# JTAG_Reset_Connection.net
KiCad netlist of a schematic drawn in Altium Designer
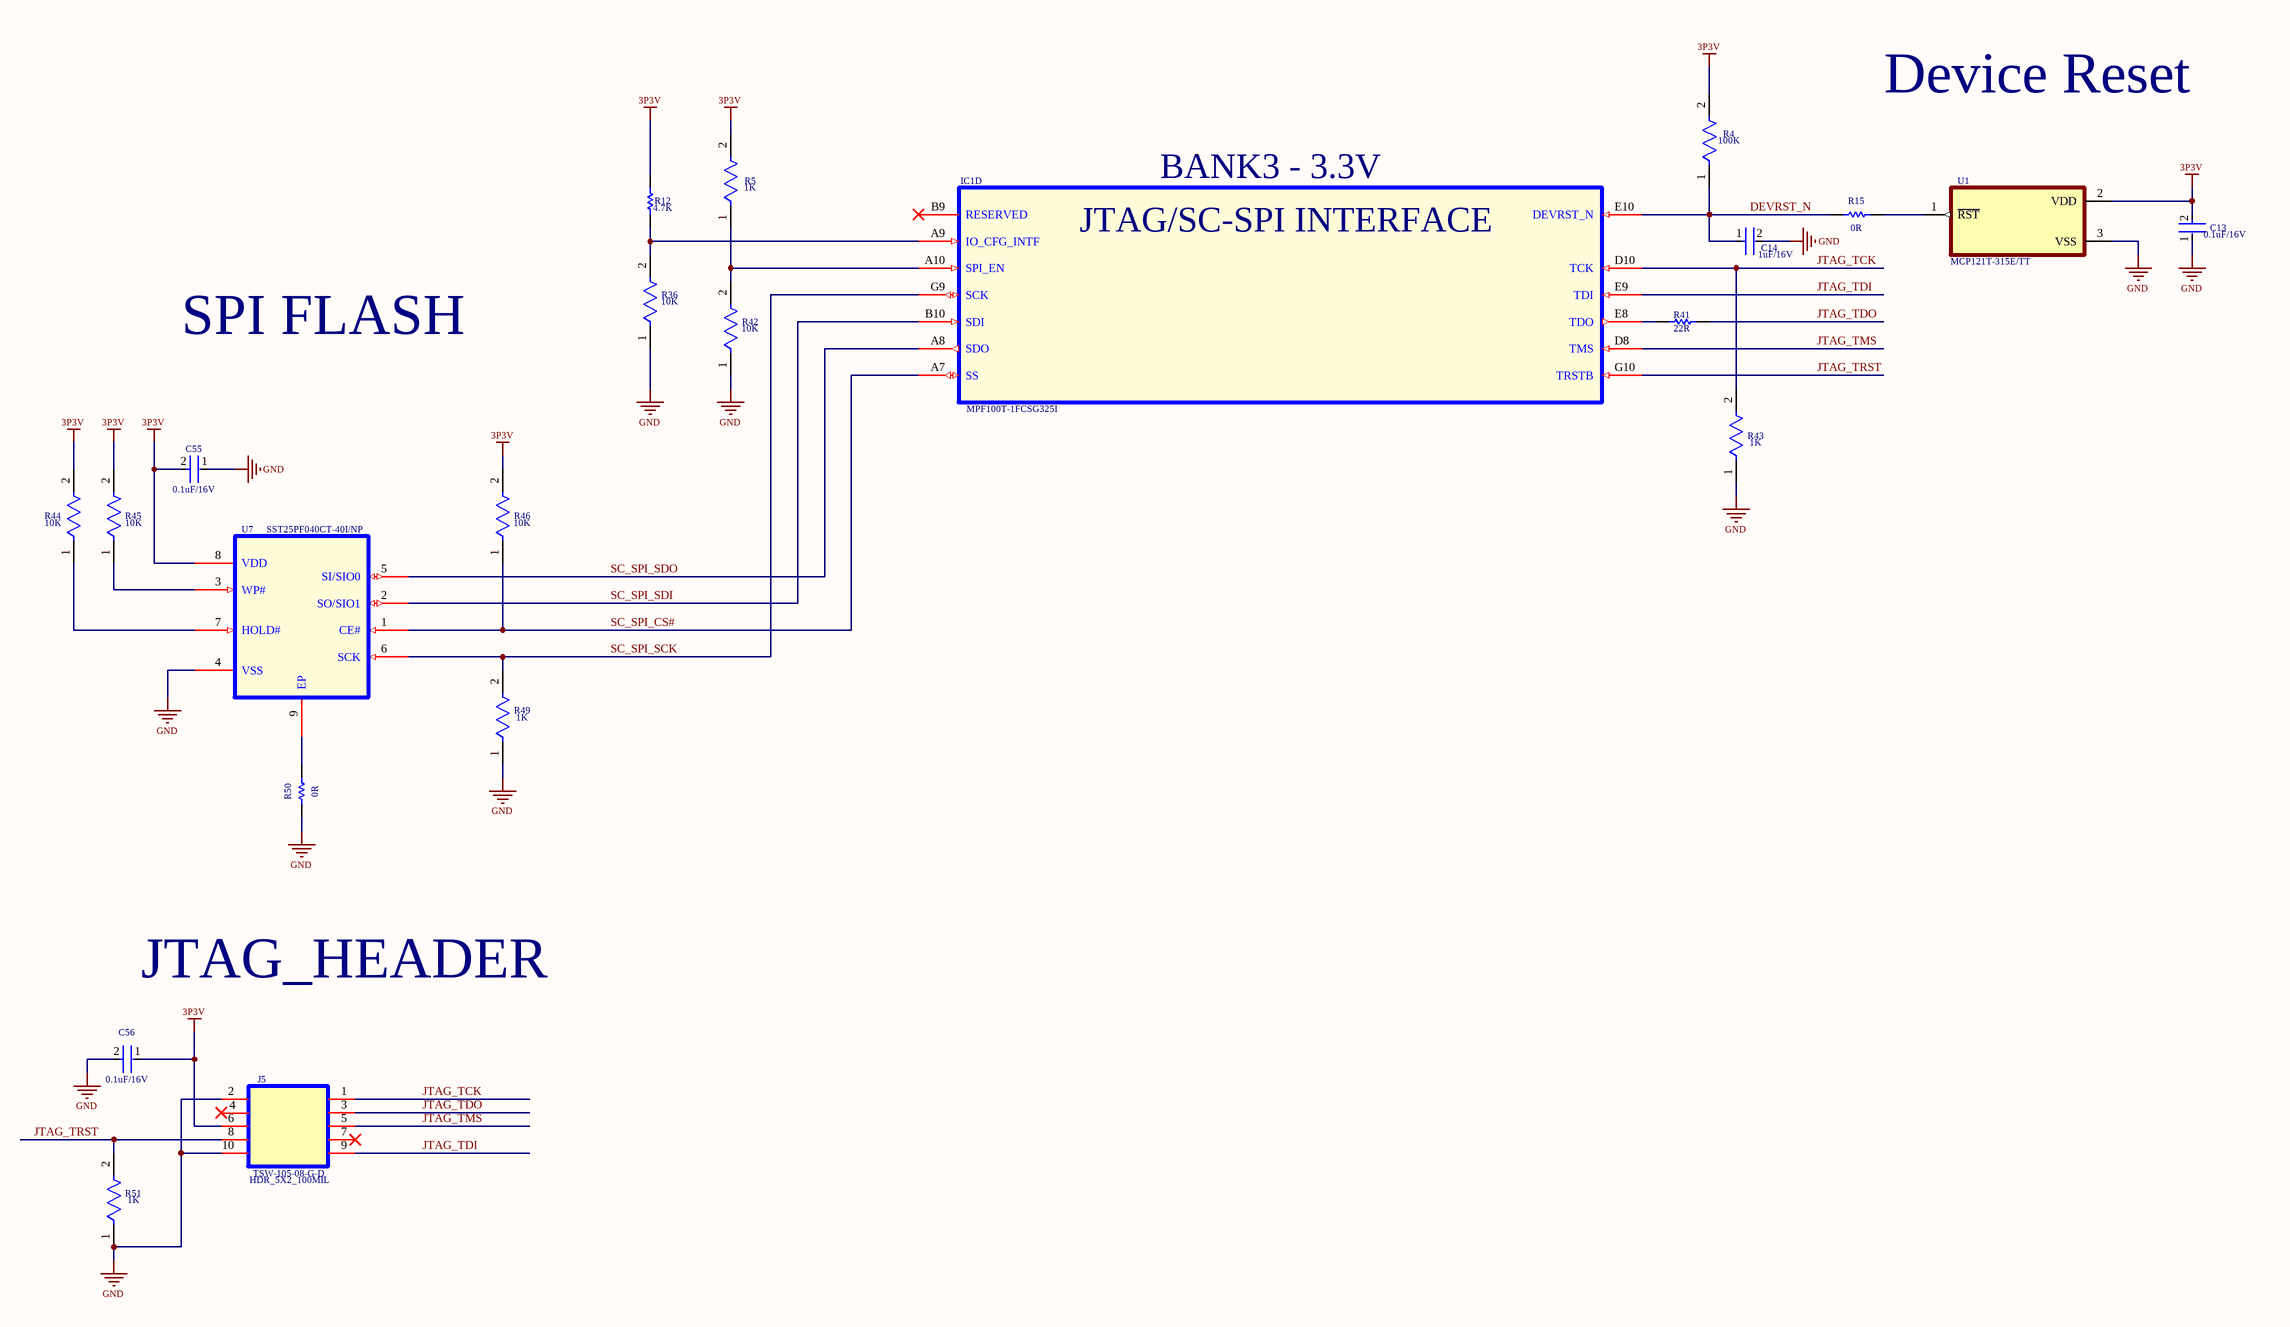
[diagram p0: JTAG & Reset Connection.SchDoc]

(export (version "E")
  (design (tool "Eeschema 10.0.6"))
  (components
    (comp (ref "C13")
      (value "0.1uF/16V")
      (footprint "FP-GRM15-MFG")
      (description "CAP CER 0.1UF 16V X7R 0402")
      (fields (field (name "MANUFACTURER PART NUMBER") "GRM155R71C104KA88D") (field (name "TOLERANCE") "10%"))
      (libsource (lib "Altium Content Vault") (part "236180d848d6139a670b325ea6854c9"))
    )
    (comp (ref "C14")
      (value "1uF/16V")
      (footprint "FP-0402-L_1_0_0_05-W_0_5-IPC_A")
      (description "None")
      (fields (field (name "TOLERANCE") "10%"))
      (libsource (lib "Altium Content Vault") (part "b4654b650e69147ec39a6b967a45e02"))
    )
    (comp (ref "C55")
      (value "0.1uF/16V")
      (footprint "FP-GRM15-MFG")
      (description "CAP CER 0.1UF 16V X7R 0402")
      (fields (field (name "MANUFACTURER PART NUMBER") "GRM155R71C104KA88D") (field (name "TOLERANCE") "10%"))
      (libsource (lib "Altium Content Vault") (part "236180d848d6139a670b325ea6854c9"))
    )
    (comp (ref "C56")
      (value "0.1uF/16V")
      (footprint "FP-GRM15-MFG")
      (description "CAP CER 0.1UF 16V X7R 0402")
      (fields (field (name "MANUFACTURER PART NUMBER") "GRM155R71C104KA88D") (field (name "TOLERANCE") "10%"))
      (libsource (lib "Altium Content Vault") (part "236180d848d6139a670b325ea6854c9"))
    )
    (comp (ref "IC1")
      (value "MPF100T-1FCSG325I")
      (footprint "PCB_Display_Doru:MPF100T-1FCSG325I")
      (fields (field (name "PART_NUMBER") "J00001"))
      (libsource (lib "PCB_Display_Doru") (part "MPF100T-1FCSG325I"))
    )
    (comp (ref "J5")
      (value "TSW-105-08-G-D")
      (footprint "PCB_Display_Doru:TSW-105-08-G-D")
      (description "Jumper")
      (fields (field (name "PART_NUMBER") "J00001") (field (name "PARAMETER 1") "HDR_5X2_100MIL"))
      (libsource (lib "PCB_Display_Doru") (part "TSW-105-08-G-D"))
    )
    (comp (ref "R4")
      (value "100K")
      (footprint "FP-RC0603-0_55-MFG")
      (description "RES SMD 100K OHM 1% 1/10W 0603")
      (fields (field (name "TOLERANCE") "1%"))
      (libsource (lib "Altium Content Vault") (part "1029c3af85768c4190bb7ad29bc67b5"))
    )
    (comp (ref "R5")
      (value "1K")
      (footprint "FP-RC0603-0_55-IPC_C")
      (description "RES 1K OHM 1% 1/10W 0603")
      (fields (field (name "TOLERANCE") "1%"))
      (libsource (lib "Altium Content Vault") (part "1029c3af85768c4190bb7ad29bc67b5"))
    )
    (comp (ref "R12")
      (value "4.7K")
      (footprint "RESC1608X55X25LL10T15")
      (description "Chip Resistor, 4.7 KOhm, +/- 1%, 0.1 W, -55 to 155 degC, 0603 (1608 Metric), RoHS, Tape and Reel")
      (fields (field (name "MANUFACTURER") "Yageo") (field (name "TOLERANCE") "1%"))
      (libsource (lib "Altium Content Vault") (part "RES-2"))
    )
    (comp (ref "R15")
      (value "0R")
      (footprint "RESC1005X40X25NL05T10")
      (fields (field (name "MANUFACTURER") "Yageo / Phycomp") (field (name "PART NUMBER") "RC0402JR-070RL"))
      (libsource (lib "Altium Content Vault") (part "RES"))
    )
    (comp (ref "R36")
      (value "10K")
      (footprint "FP-RC0603-0_55-IPC_C")
      (description "RES 10K OHM 1% 1/10W 0603")
      (fields (field (name "TOLERANCE") "1%"))
      (libsource (lib "Altium Content Vault") (part "1029c3af85768c4190bb7ad29bc67b5"))
    )
    (comp (ref "R41")
      (value "22R")
      (footprint "RESC1005X40X25LL05T10")
      (fields (field (name "MANUFACTURER") "Yageo / Phycomp") (field (name "PART NUMBER") "RC0402FR-0722RL"))
      (libsource (lib "Altium Content Vault") (part "RES"))
    )
    (comp (ref "R42")
      (value "10K")
      (footprint "FP-RC0603-0_55-IPC_C")
      (description "RES 10K OHM 1% 1/10W 0603")
      (fields (field (name "TOLERANCE") "1%"))
      (libsource (lib "Altium Content Vault") (part "1029c3af85768c4190bb7ad29bc67b5"))
    )
    (comp (ref "R43")
      (value "1K")
      (footprint "FP-RC0603-0_55-IPC_C")
      (description "RES 1K OHM 1% 1/10W 0603")
      (fields (field (name "TOLERANCE") "1%"))
      (libsource (lib "Altium Content Vault") (part "1029c3af85768c4190bb7ad29bc67b5"))
    )
    (comp (ref "R44")
      (value "10K")
      (footprint "FP-RC0603-0_55-IPC_C")
      (description "RES 10K OHM 1% 1/10W 0603")
      (fields (field (name "TOLERANCE") "1%"))
      (libsource (lib "Altium Content Vault") (part "1029c3af85768c4190bb7ad29bc67b5"))
    )
    (comp (ref "R45")
      (value "10K")
      (footprint "FP-RC0603-0_55-IPC_C")
      (description "RES 10K OHM 1% 1/10W 0603")
      (fields (field (name "TOLERANCE") "1%"))
      (libsource (lib "Altium Content Vault") (part "1029c3af85768c4190bb7ad29bc67b5"))
    )
    (comp (ref "R46")
      (value "10K")
      (footprint "FP-RC0603-0_55-IPC_C")
      (description "RES 10K OHM 1% 1/10W 0603")
      (fields (field (name "TOLERANCE") "1%"))
      (libsource (lib "Altium Content Vault") (part "1029c3af85768c4190bb7ad29bc67b5"))
    )
    (comp (ref "R49")
      (value "1K")
      (footprint "FP-RC0603-0_55-IPC_C")
      (description "RES 1K OHM 1% 1/10W 0603")
      (fields (field (name "TOLERANCE") "1%"))
      (libsource (lib "Altium Content Vault") (part "1029c3af85768c4190bb7ad29bc67b5"))
    )
    (comp (ref "R50")
      (value "0R")
      (footprint "RESC1005X40X25NL05T10")
      (fields (field (name "MANUFACTURER") "Yageo / Phycomp") (field (name "PART NUMBER") "RC0402JR-070RL"))
      (libsource (lib "Altium Content Vault") (part "RES"))
    )
    (comp (ref "R51")
      (value "1K")
      (footprint "FP-RC0603-0_55-IPC_C")
      (description "RES 1K OHM 1% 1/10W 0603")
      (fields (field (name "TOLERANCE") "1%"))
      (libsource (lib "Altium Content Vault") (part "1029c3af85768c4190bb7ad29bc67b5"))
    )
    (comp (ref "U1")
      (value "MCP121T-315E/TT")
      (footprint "PCB_Display_Doru:MCP121T-315E/TT")
      (description "Jumper")
      (fields (field (name "PART_NUMBER") "J00001"))
      (libsource (lib "PCB_Display_Doru") (part "MCP121T-315E/TT"))
    )
    (comp (ref "U7")
      (value "SST25PF040CT-40I/NP")
      (footprint "PCB_Display_Doru:SST25PF040CT-40I/NP")
      (description "Jumper")
      (fields (field (name "PART_NUMBER") "J00001"))
      (libsource (lib "PCB_Display_Doru") (part "SST25PF040CT-40I/NP"))
    )
  )
  (nets
    (net (code "1") (name "/DEVRST_N") (class "Default")
      (node (ref "C14") (pin "1") (pinfunction "1_1") (pintype "passive"))
      (node (ref "IC1") (pin "E10") (pinfunction "DEVRST_N_E10") (pintype "input"))
      (node (ref "R15") (pin "1") (pinfunction "1_1") (pintype "passive"))
      (node (ref "R4") (pin "1") (pinfunction "1_1") (pintype "passive"))
    )
    (net (code "2") (name "/JTAG_TCK") (class "Default")
      (node (ref "IC1") (pin "D10") (pinfunction "TCK_D10") (pintype "input"))
      (node (ref "J5") (pin "1") (pinfunction "02_1") (pintype "passive"))
      (node (ref "R43") (pin "2") (pinfunction "2_2") (pintype "passive"))
    )
    (net (code "3") (name "/JTAG_TDI") (class "Default")
      (node (ref "IC1") (pin "E9") (pinfunction "TDI_E9") (pintype "input"))
      (node (ref "J5") (pin "9") (pinfunction "10_9") (pintype "passive"))
    )
    (net (code "4") (name "/JTAG_TDO") (class "Default")
      (node (ref "J5") (pin "3") (pinfunction "04_3") (pintype "passive"))
      (node (ref "R41") (pin "1") (pinfunction "1_1") (pintype "passive"))
    )
    (net (code "5") (name "/JTAG_TMS") (class "Default")
      (node (ref "IC1") (pin "D8") (pinfunction "TMS_D8") (pintype "input"))
      (node (ref "J5") (pin "5") (pinfunction "06_5") (pintype "passive"))
    )
    (net (code "6") (name "/JTAG_TRST") (class "Default")
      (node (ref "IC1") (pin "G10") (pinfunction "TRSTB_G10") (pintype "input"))
      (node (ref "J5") (pin "8") (pinfunction "07_8") (pintype "passive"))
      (node (ref "R51") (pin "2") (pinfunction "2_2") (pintype "passive"))
    )
    (net (code "7") (name "/SC_SPI_CS#") (class "Default")
      (node (ref "IC1") (pin "A7") (pinfunction "SS_A7") (pintype "bidirectional"))
      (node (ref "R46") (pin "1") (pinfunction "1_1") (pintype "passive"))
      (node (ref "U7") (pin "1") (pinfunction "CE#_1") (pintype "input"))
    )
    (net (code "8") (name "/SC_SPI_SCK") (class "Default")
      (node (ref "IC1") (pin "G9") (pinfunction "SCK_G9") (pintype "bidirectional"))
      (node (ref "R49") (pin "2") (pinfunction "2_2") (pintype "passive"))
      (node (ref "U7") (pin "6") (pinfunction "SCK_6") (pintype "input"))
    )
    (net (code "9") (name "/SC_SPI_SDI") (class "Default")
      (node (ref "IC1") (pin "B10") (pinfunction "SDI_B10") (pintype "input"))
      (node (ref "U7") (pin "2") (pinfunction "SO/SIO1_2") (pintype "bidirectional"))
    )
    (net (code "10") (name "/SC_SPI_SDO") (class "Default")
      (node (ref "IC1") (pin "A8") (pinfunction "SDO_A8") (pintype "output"))
      (node (ref "U7") (pin "5") (pinfunction "SI/SIO0_5") (pintype "bidirectional"))
    )
    (net (code "11") (name "3P3V") (class "Default")
      (node (ref "C13") (pin "2") (pinfunction "2_2") (pintype "passive"))
      (node (ref "C55") (pin "2") (pinfunction "2_2") (pintype "passive"))
      (node (ref "C56") (pin "1") (pinfunction "1_1") (pintype "passive"))
      (node (ref "J5") (pin "6") (pinfunction "6_6") (pintype "passive"))
      (node (ref "R12") (pin "2") (pinfunction "2_2") (pintype "passive"))
      (node (ref "R4") (pin "2") (pinfunction "2_2") (pintype "passive"))
      (node (ref "R44") (pin "2") (pinfunction "2_2") (pintype "passive"))
      (node (ref "R45") (pin "2") (pinfunction "2_2") (pintype "passive"))
      (node (ref "R46") (pin "2") (pinfunction "2_2") (pintype "passive"))
      (node (ref "R5") (pin "2") (pinfunction "2_2") (pintype "passive"))
      (node (ref "U1") (pin "2") (pinfunction "VDD_2") (pintype "power_in"))
      (node (ref "U7") (pin "8") (pinfunction "VDD_8") (pintype "power_in"))
    )
    (net (code "12") (name "GND") (class "Default")
      (node (ref "C13") (pin "1") (pinfunction "1_1") (pintype "passive"))
      (node (ref "C14") (pin "2") (pinfunction "2_2") (pintype "passive"))
      (node (ref "C55") (pin "1") (pinfunction "1_1") (pintype "passive"))
      (node (ref "C56") (pin "2") (pinfunction "2_2") (pintype "passive"))
      (node (ref "J5") (pin "10") (pinfunction "09_10") (pintype "passive"))
      (node (ref "J5") (pin "2") (pinfunction "01_2") (pintype "passive"))
      (node (ref "R36") (pin "1") (pinfunction "1_1") (pintype "passive"))
      (node (ref "R42") (pin "1") (pinfunction "1_1") (pintype "passive"))
      (node (ref "R43") (pin "1") (pinfunction "1_1") (pintype "passive"))
      (node (ref "R49") (pin "1") (pinfunction "1_1") (pintype "passive"))
      (node (ref "R50") (pin "1") (pinfunction "1_1") (pintype "passive"))
      (node (ref "R51") (pin "1") (pinfunction "1_1") (pintype "passive"))
      (node (ref "U1") (pin "3") (pinfunction "VSS_3") (pintype "power_in"))
      (node (ref "U7") (pin "4") (pinfunction "VSS_4") (pintype "power_in"))
    )
    (net (code "13") (name "Net-(IC1D-IO_CFG_INTF)") (class "Default")
      (node (ref "IC1") (pin "A9") (pinfunction "IO_CFG_INTF_A9") (pintype "input"))
      (node (ref "R12") (pin "1") (pinfunction "1_1") (pintype "passive"))
      (node (ref "R36") (pin "2") (pinfunction "2_2") (pintype "passive"))
    )
    (net (code "14") (name "Net-(IC1D-SPI_EN)") (class "Default")
      (node (ref "IC1") (pin "A10") (pinfunction "SPI_EN_A10") (pintype "input"))
      (node (ref "R42") (pin "2") (pinfunction "2_2") (pintype "passive"))
      (node (ref "R5") (pin "1") (pinfunction "1_1") (pintype "passive"))
    )
    (net (code "15") (name "Net-(IC1D-TDO)") (class "Default")
      (node (ref "IC1") (pin "E8") (pinfunction "TDO_E8") (pintype "output"))
      (node (ref "R41") (pin "2") (pinfunction "2_2") (pintype "passive"))
    )
    (net (code "16") (name "Net-(U1-~{RST})") (class "Default")
      (node (ref "R15") (pin "2") (pinfunction "2_2") (pintype "passive"))
      (node (ref "U1") (pin "1") (pinfunction "~{RST}_1") (pintype "output"))
    )
    (net (code "17") (name "Net-(U7-EP)") (class "Default")
      (node (ref "R50") (pin "2") (pinfunction "2_2") (pintype "passive"))
      (node (ref "U7") (pin "9") (pinfunction "EP_9") (pintype "power_in"))
    )
    (net (code "18") (name "Net-(U7-HOLD#)") (class "Default")
      (node (ref "R44") (pin "1") (pinfunction "1_1") (pintype "passive"))
      (node (ref "U7") (pin "7") (pinfunction "HOLD#_7") (pintype "input"))
    )
    (net (code "19") (name "Net-(U7-WP#)") (class "Default")
      (node (ref "R45") (pin "1") (pinfunction "1_1") (pintype "passive"))
      (node (ref "U7") (pin "3") (pinfunction "WP#_3") (pintype "input"))
    )
    (net (code "20") (name "unconnected-(IC1D-RESERVED-PadB9)") (class "Default")
      (node (ref "IC1") (pin "B9") (pinfunction "RESERVED_B9") (pintype "passive+no_connect"))
    )
    (net (code "21") (name "unconnected-(J5-03-Pad4)") (class "Default")
      (node (ref "J5") (pin "4") (pinfunction "03_4") (pintype "passive"))
    )
    (net (code "22") (name "unconnected-(J5-08-Pad7)") (class "Default")
      (node (ref "J5") (pin "7") (pinfunction "08_7") (pintype "passive+no_connect"))
    )
  )
)
